# CEF_JFET.net
KiCad netlist of a schematic drawn in Altium Designer
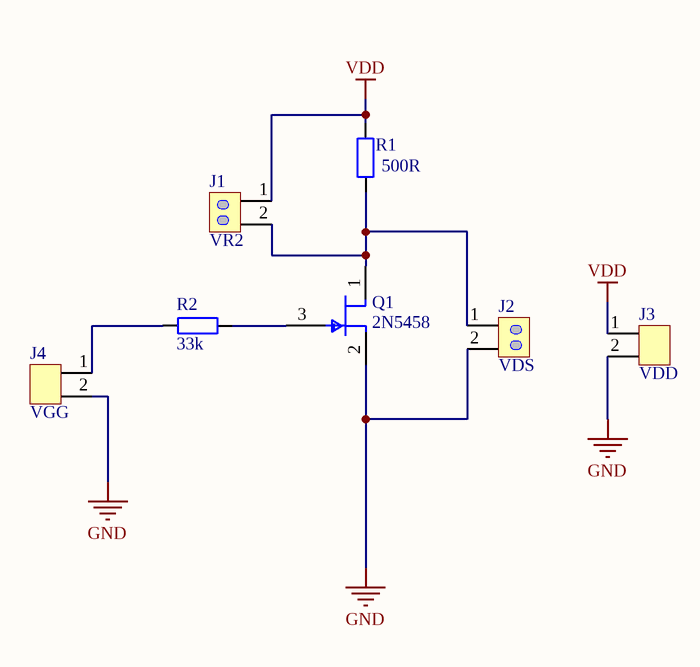
[diagram p0: CEF JFET.SchDoc]

(export (version "E")
  (design (tool "Eeschema 10.0.6"))
  (components
    (comp (ref "J1")
      (value "VR2")
      (footprint "HDR_1x2_pin")
      (description "Header, 2-Pin")
      (libsource (lib "CEF") (part "HDR_1x2"))
    )
    (comp (ref "J2")
      (value "VDS")
      (footprint "HDR_1x2_pin")
      (description "Header, 2-Pin")
      (libsource (lib "") (part "HDR_1x2_1"))
    )
    (comp (ref "J3")
      (value "VDD")
      (footprint "HDR_1X2_TE")
      (description "Connector, 2-Ports")
      (libsource (lib "CEF") (part "CON_1x2"))
    )
    (comp (ref "J4")
      (value "VGG")
      (footprint "HDR_1X2_TE")
      (description "Connector, 2-Ports")
      (libsource (lib "") (part "CON_1x2_1"))
    )
    (comp (ref "Q1")
      (value "2N5458")
      (footprint "FP-29-11-MFG")
      (libsource (lib "Altium Content Vault") (part "2fe1325ee7984bd9864bb4197617735"))
    )
    (comp (ref "R1")
      (value "500R")
      (footprint "Resistor")
      (description "0.25W,Axial")
      (libsource (lib "CEF") (part "Resistor 0.25W 5mm"))
    )
    (comp (ref "R2")
      (value "33k")
      (footprint "Resistor")
      (description "0.25W,Axial")
      (libsource (lib "CEF") (part "Resistor 0.25W 5mm"))
    )
  )
  (nets
    (net (code "1") (name "GND") (class "Default")
      (node (ref "J2") (pin "2") (pinfunction "2_2") (pintype "passive"))
      (node (ref "J3") (pin "2") (pinfunction "2_2") (pintype "passive"))
      (node (ref "J4") (pin "2") (pinfunction "2_2") (pintype "passive"))
      (node (ref "Q1") (pin "2") (pinfunction "SOURCE_2") (pintype "passive"))
    )
    (net (code "2") (name "Net-(J4-Pad1)") (class "Default")
      (node (ref "J4") (pin "1") (pinfunction "1_1") (pintype "passive"))
      (node (ref "R2") (pin "1") (pinfunction "1_1") (pintype "passive"))
    )
    (net (code "3") (name "Net-(Q1-DRAIN)") (class "Default")
      (node (ref "J1") (pin "2") (pinfunction "2_2") (pintype "passive"))
      (node (ref "J2") (pin "1") (pinfunction "1_1") (pintype "passive"))
      (node (ref "Q1") (pin "1") (pinfunction "DRAIN_1") (pintype "passive"))
      (node (ref "R1") (pin "1") (pinfunction "1_1") (pintype "passive"))
    )
    (net (code "4") (name "Net-(Q1-GATE)") (class "Default")
      (node (ref "Q1") (pin "3") (pinfunction "GATE_3") (pintype "passive"))
      (node (ref "R2") (pin "2") (pinfunction "2_2") (pintype "passive"))
    )
    (net (code "5") (name "VDD") (class "Default")
      (node (ref "J1") (pin "1") (pinfunction "1_1") (pintype "passive"))
      (node (ref "J3") (pin "1") (pinfunction "1_1") (pintype "passive"))
      (node (ref "R1") (pin "2") (pinfunction "2_2") (pintype "passive"))
    )
  )
)
